# projectElectro.net
KiCad netlist of a schematic drawn in EAGLE
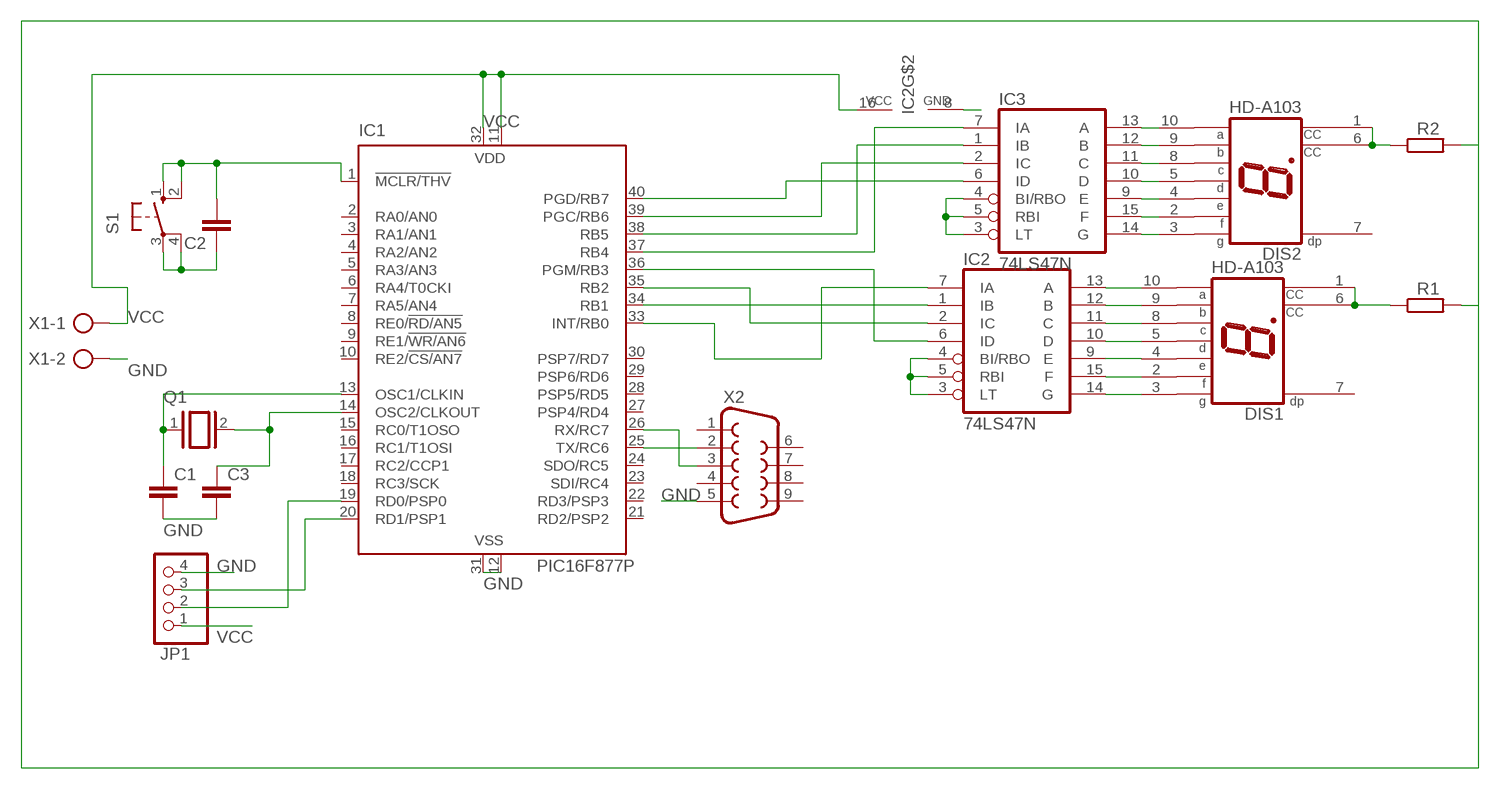
[diagram p0: schematic, sheet 1]

(export (version "E")
  (design (tool "Eeschema 10.0.6"))
  (components
    (comp (ref "C1")
      (value "C-EU025-025X050")
      (footprint "eagle-import:C025-025X050")
      (libsource (lib "eagle-import") (part "C-EU025-025X050"))
    )
    (comp (ref "C2")
      (value "C-EU025-025X050")
      (footprint "eagle-import:C025-025X050")
      (libsource (lib "eagle-import") (part "C-EU025-025X050"))
    )
    (comp (ref "C3")
      (value "C-EU025-025X050")
      (footprint "eagle-import:C025-025X050")
      (libsource (lib "eagle-import") (part "C-EU025-025X050"))
    )
    (comp (ref "DIS1")
      (value "HD-A103")
      (footprint "eagle-import:HDSP-A")
      (libsource (lib "eagle-import") (part "HD-A103"))
    )
    (comp (ref "DIS2")
      (value "HD-A103")
      (footprint "eagle-import:HDSP-A")
      (libsource (lib "eagle-import") (part "HD-A103"))
    )
    (comp (ref "IC1")
      (value "PIC16F877P")
      (footprint "eagle-import:DIL40")
      (fields (field (name "MF") "MICROCHIP") (field (name "MPN") "PIC16F877-04/P"))
      (libsource (lib "eagle-import") (part "PIC16F87P7"))
    )
    (comp (ref "IC2")
      (value "74LS47N")
      (footprint "eagle-import:DIL16")
      (libsource (lib "eagle-import") (part "7447NLS"))
    )
    (comp (ref "IC3")
      (value "74LS47N")
      (footprint "eagle-import:DIL16")
      (libsource (lib "eagle-import") (part "7447NLS"))
    )
    (comp (ref "JP1")
      (value "PINHD-1X4")
      (footprint "eagle-import:1X04")
      (libsource (lib "eagle-import") (part "PINHD-1X4"))
    )
    (comp (ref "Q1")
      (value "XTAL/S")
      (footprint "eagle-import:QS")
      (libsource (lib "eagle-import") (part "XTAL/S"))
    )
    (comp (ref "R1")
      (value "R-EU_0207/10")
      (footprint "eagle-import:0207_10")
      (libsource (lib "eagle-import") (part "R-EU_0207/10"))
    )
    (comp (ref "R2")
      (value "R-EU_0207/10")
      (footprint "eagle-import:0207_10")
      (libsource (lib "eagle-import") (part "R-EU_0207/10"))
    )
    (comp (ref "S1")
      (value "10-XX")
      (footprint "eagle-import:B3F-10XX")
      (fields (field (name "MPN") "B3F-1000"))
      (libsource (lib "eagle-import") (part "10-XX"))
    )
    (comp (ref "X1")
      (value "AK300/2")
      (footprint "eagle-import:AK300_2")
      (libsource (lib "eagle-import") (part "AK300/2"))
    )
    (comp (ref "X2")
      (value "F09H")
      (footprint "eagle-import:F09H")
      (libsource (lib "eagle-import") (part "F09H"))
    )
  )
  (nets
    (net (code "1") (name "/GND") (class "Default")
      (node (ref "C1") (pin "2") (pinfunction "2_2") (pintype "passive"))
      (node (ref "C3") (pin "2") (pinfunction "2_2") (pintype "passive"))
      (node (ref "IC1") (pin "12") (pinfunction "VSS_12") (pintype "power_in"))
      (node (ref "IC1") (pin "31") (pinfunction "VSS_31") (pintype "power_in"))
      (node (ref "JP1") (pin "4") (pinfunction "4_4") (pintype "passive"))
      (node (ref "X1") (pin "2") (pinfunction "KL_2") (pintype "passive"))
      (node (ref "X2") (pin "5") (pinfunction "5_5") (pintype "passive"))
    )
    (net (code "2") (name "/VCC") (class "Default")
      (node (ref "IC1") (pin "11") (pinfunction "VDD_11") (pintype "power_in"))
      (node (ref "IC1") (pin "32") (pinfunction "VDD_32") (pintype "power_in"))
      (node (ref "IC2") (pin "16") (pinfunction "VCC_16") (pintype "power_in"))
      (node (ref "JP1") (pin "1") (pinfunction "1_1") (pintype "passive"))
      (node (ref "X1") (pin "1") (pinfunction "KL_1") (pintype "passive"))
    )
    (net (code "3") (name "Net-(DIS1-A)") (class "Default")
      (node (ref "DIS1") (pin "10") (pinfunction "A_10") (pintype "passive"))
      (node (ref "IC2") (pin "13") (pinfunction "A_13") (pintype "output"))
    )
    (net (code "4") (name "Net-(DIS1-B)") (class "Default")
      (node (ref "DIS1") (pin "9") (pinfunction "B_9") (pintype "passive"))
      (node (ref "IC2") (pin "12") (pinfunction "B_12") (pintype "output"))
    )
    (net (code "5") (name "Net-(DIS1-C)") (class "Default")
      (node (ref "DIS1") (pin "8") (pinfunction "C_8") (pintype "passive"))
      (node (ref "IC2") (pin "11") (pinfunction "C_11") (pintype "output"))
    )
    (net (code "6") (name "Net-(DIS1-CC-Pad1)") (class "Default")
      (node (ref "DIS1") (pin "1") (pinfunction "CC_1") (pintype "passive"))
      (node (ref "DIS1") (pin "6") (pinfunction "CC_6") (pintype "passive"))
      (node (ref "R1") (pin "1") (pinfunction "1_1") (pintype "passive"))
    )
    (net (code "7") (name "Net-(DIS1-D)") (class "Default")
      (node (ref "DIS1") (pin "5") (pinfunction "D_5") (pintype "passive"))
      (node (ref "IC2") (pin "10") (pinfunction "D_10") (pintype "output"))
    )
    (net (code "8") (name "Net-(DIS1-E)") (class "Default")
      (node (ref "DIS1") (pin "4") (pinfunction "E_4") (pintype "passive"))
      (node (ref "IC2") (pin "9") (pinfunction "E_9") (pintype "output"))
    )
    (net (code "9") (name "Net-(DIS1-F)") (class "Default")
      (node (ref "DIS1") (pin "2") (pinfunction "F_2") (pintype "passive"))
      (node (ref "IC2") (pin "15") (pinfunction "F_15") (pintype "output"))
    )
    (net (code "10") (name "Net-(DIS1-G)") (class "Default")
      (node (ref "DIS1") (pin "3") (pinfunction "G_3") (pintype "passive"))
      (node (ref "IC2") (pin "14") (pinfunction "G_14") (pintype "output"))
    )
    (net (code "11") (name "Net-(DIS2-A)") (class "Default")
      (node (ref "DIS2") (pin "10") (pinfunction "A_10") (pintype "passive"))
      (node (ref "IC3") (pin "13") (pinfunction "A_13") (pintype "output"))
    )
    (net (code "12") (name "Net-(DIS2-B)") (class "Default")
      (node (ref "DIS2") (pin "9") (pinfunction "B_9") (pintype "passive"))
      (node (ref "IC3") (pin "12") (pinfunction "B_12") (pintype "output"))
    )
    (net (code "13") (name "Net-(DIS2-C)") (class "Default")
      (node (ref "DIS2") (pin "8") (pinfunction "C_8") (pintype "passive"))
      (node (ref "IC3") (pin "11") (pinfunction "C_11") (pintype "output"))
    )
    (net (code "14") (name "Net-(DIS2-CC-Pad1)") (class "Default")
      (node (ref "DIS2") (pin "1") (pinfunction "CC_1") (pintype "passive"))
      (node (ref "DIS2") (pin "6") (pinfunction "CC_6") (pintype "passive"))
      (node (ref "R2") (pin "1") (pinfunction "1_1") (pintype "passive"))
    )
    (net (code "15") (name "Net-(DIS2-D)") (class "Default")
      (node (ref "DIS2") (pin "5") (pinfunction "D_5") (pintype "passive"))
      (node (ref "IC3") (pin "10") (pinfunction "D_10") (pintype "output"))
    )
    (net (code "16") (name "Net-(DIS2-E)") (class "Default")
      (node (ref "DIS2") (pin "4") (pinfunction "E_4") (pintype "passive"))
      (node (ref "IC3") (pin "9") (pinfunction "E_9") (pintype "output"))
    )
    (net (code "17") (name "Net-(DIS2-F)") (class "Default")
      (node (ref "DIS2") (pin "2") (pinfunction "F_2") (pintype "passive"))
      (node (ref "IC3") (pin "15") (pinfunction "F_15") (pintype "output"))
    )
    (net (code "18") (name "Net-(DIS2-G)") (class "Default")
      (node (ref "DIS2") (pin "3") (pinfunction "G_3") (pintype "passive"))
      (node (ref "IC3") (pin "14") (pinfunction "G_14") (pintype "output"))
    )
    (net (code "19") (name "Net-(IC1-INT{slash}RB0)") (class "Default")
      (node (ref "IC1") (pin "33") (pinfunction "INT/RB0_33") (pintype "bidirectional"))
      (node (ref "IC2") (pin "7") (pinfunction "IA_7") (pintype "input"))
    )
    (net (code "20") (name "Net-(IC1-OSC1{slash}CLKIN)") (class "Default")
      (node (ref "C1") (pin "1") (pinfunction "1_1") (pintype "passive"))
      (node (ref "IC1") (pin "13") (pinfunction "OSC1/CLKIN_13") (pintype "input"))
      (node (ref "Q1") (pin "1") (pinfunction "1_1") (pintype "passive"))
    )
    (net (code "21") (name "Net-(IC1-OSC2{slash}CLKOUT)") (class "Default")
      (node (ref "C3") (pin "1") (pinfunction "1_1") (pintype "passive"))
      (node (ref "IC1") (pin "14") (pinfunction "OSC2/CLKOUT_14") (pintype "output"))
      (node (ref "Q1") (pin "2") (pinfunction "2_2") (pintype "passive"))
    )
    (net (code "22") (name "Net-(IC1-PGC{slash}RB6)") (class "Default")
      (node (ref "IC1") (pin "39") (pinfunction "PGC/RB6_39") (pintype "bidirectional"))
      (node (ref "IC3") (pin "2") (pinfunction "IC_2") (pintype "input"))
    )
    (net (code "23") (name "Net-(IC1-PGD{slash}RB7)") (class "Default")
      (node (ref "IC1") (pin "40") (pinfunction "PGD/RB7_40") (pintype "bidirectional"))
      (node (ref "IC3") (pin "6") (pinfunction "ID_6") (pintype "input"))
    )
    (net (code "24") (name "Net-(IC1-PGM{slash}RB3)") (class "Default")
      (node (ref "IC1") (pin "36") (pinfunction "PGM/RB3_36") (pintype "bidirectional"))
      (node (ref "IC2") (pin "6") (pinfunction "ID_6") (pintype "input"))
    )
    (net (code "25") (name "Net-(IC1-RB1)") (class "Default")
      (node (ref "IC1") (pin "34") (pinfunction "RB1_34") (pintype "bidirectional"))
      (node (ref "IC2") (pin "1") (pinfunction "IB_1") (pintype "input"))
    )
    (net (code "26") (name "Net-(IC1-RB2)") (class "Default")
      (node (ref "IC1") (pin "35") (pinfunction "RB2_35") (pintype "bidirectional"))
      (node (ref "IC2") (pin "2") (pinfunction "IC_2") (pintype "input"))
    )
    (net (code "27") (name "Net-(IC1-RB4)") (class "Default")
      (node (ref "IC1") (pin "37") (pinfunction "RB4_37") (pintype "bidirectional"))
      (node (ref "IC3") (pin "7") (pinfunction "IA_7") (pintype "input"))
    )
    (net (code "28") (name "Net-(IC1-RB5)") (class "Default")
      (node (ref "IC1") (pin "38") (pinfunction "RB5_38") (pintype "bidirectional"))
      (node (ref "IC3") (pin "1") (pinfunction "IB_1") (pintype "input"))
    )
    (net (code "29") (name "Net-(IC1-RD0{slash}PSP0)") (class "Default")
      (node (ref "IC1") (pin "19") (pinfunction "RD0/PSP0_19") (pintype "bidirectional"))
      (node (ref "JP1") (pin "2") (pinfunction "2_2") (pintype "passive"))
    )
    (net (code "30") (name "Net-(IC1-RD1{slash}PSP1)") (class "Default")
      (node (ref "IC1") (pin "20") (pinfunction "RD1/PSP1_20") (pintype "bidirectional"))
      (node (ref "JP1") (pin "3") (pinfunction "3_3") (pintype "passive"))
    )
    (net (code "31") (name "Net-(IC1-RX{slash}RC7)") (class "Default")
      (node (ref "IC1") (pin "26") (pinfunction "RX/RC7_26") (pintype "bidirectional"))
      (node (ref "X2") (pin "3") (pinfunction "3_3") (pintype "passive"))
    )
    (net (code "32") (name "Net-(IC1-TX{slash}RC6)") (class "Default")
      (node (ref "IC1") (pin "25") (pinfunction "TX/RC6_25") (pintype "bidirectional"))
      (node (ref "X2") (pin "2") (pinfunction "2_2") (pintype "passive"))
    )
    (net (code "33") (name "Net-(IC1-~{MCLR{slash}THV})") (class "Default")
      (node (ref "C2") (pin "2") (pinfunction "2_2") (pintype "passive"))
      (node (ref "IC1") (pin "1") (pinfunction "~{MCLR/THV}_1") (pintype "input"))
      (node (ref "S1") (pin "1") (pinfunction "S_1") (pintype "passive"))
      (node (ref "S1") (pin "2") (pinfunction "S1_2") (pintype "passive"))
    )
    (net (code "34") (name "Net-(IC2A-BI{slash}RBO)") (class "Default")
      (node (ref "IC2") (pin "3") (pinfunction "LT_3") (pintype "input"))
      (node (ref "IC2") (pin "4") (pinfunction "BI/RBO_4") (pintype "input"))
      (node (ref "IC2") (pin "5") (pinfunction "RBI_5") (pintype "input"))
    )
    (net (code "35") (name "Net-(IC3A-BI{slash}RBO)") (class "Default")
      (node (ref "IC3") (pin "3") (pinfunction "LT_3") (pintype "input"))
      (node (ref "IC3") (pin "4") (pinfunction "BI/RBO_4") (pintype "input"))
      (node (ref "IC3") (pin "5") (pinfunction "RBI_5") (pintype "input"))
    )
    (net (code "36") (name "Net-(S1-P)") (class "Default")
      (node (ref "C2") (pin "1") (pinfunction "1_1") (pintype "passive"))
      (node (ref "S1") (pin "3") (pinfunction "P_3") (pintype "passive"))
      (node (ref "S1") (pin "4") (pinfunction "P1_4") (pintype "passive"))
    )
    (net (code "37") (name "unconnected-(DIS1-DP-Pad7)") (class "Default")
      (node (ref "DIS1") (pin "7") (pinfunction "DP_7") (pintype "passive"))
    )
    (net (code "38") (name "unconnected-(DIS2-DP-Pad7)") (class "Default")
      (node (ref "DIS2") (pin "7") (pinfunction "DP_7") (pintype "passive"))
    )
    (net (code "39") (name "unconnected-(IC1-PSP4{slash}RD4-Pad27)") (class "Default")
      (node (ref "IC1") (pin "27") (pinfunction "PSP4/RD4_27") (pintype "bidirectional"))
    )
    (net (code "40") (name "unconnected-(IC1-PSP5{slash}RD5-Pad28)") (class "Default")
      (node (ref "IC1") (pin "28") (pinfunction "PSP5/RD5_28") (pintype "bidirectional"))
    )
    (net (code "41") (name "unconnected-(IC1-PSP6{slash}RD6-Pad29)") (class "Default")
      (node (ref "IC1") (pin "29") (pinfunction "PSP6/RD6_29") (pintype "bidirectional"))
    )
    (net (code "42") (name "unconnected-(IC1-PSP7{slash}RD7-Pad30)") (class "Default")
      (node (ref "IC1") (pin "30") (pinfunction "PSP7/RD7_30") (pintype "bidirectional"))
    )
    (net (code "43") (name "unconnected-(IC1-RA0{slash}AN0-Pad2)") (class "Default")
      (node (ref "IC1") (pin "2") (pinfunction "RA0/AN0_2") (pintype "bidirectional"))
    )
    (net (code "44") (name "unconnected-(IC1-RA1{slash}AN1-Pad3)") (class "Default")
      (node (ref "IC1") (pin "3") (pinfunction "RA1/AN1_3") (pintype "bidirectional"))
    )
    (net (code "45") (name "unconnected-(IC1-RA2{slash}AN2-Pad4)") (class "Default")
      (node (ref "IC1") (pin "4") (pinfunction "RA2/AN2_4") (pintype "bidirectional"))
    )
    (net (code "46") (name "unconnected-(IC1-RA3{slash}AN3-Pad5)") (class "Default")
      (node (ref "IC1") (pin "5") (pinfunction "RA3/AN3_5") (pintype "bidirectional"))
    )
    (net (code "47") (name "unconnected-(IC1-RA4{slash}T0CKI-Pad6)") (class "Default")
      (node (ref "IC1") (pin "6") (pinfunction "RA4/T0CKI_6") (pintype "bidirectional"))
    )
    (net (code "48") (name "unconnected-(IC1-RA5{slash}AN4-Pad7)") (class "Default")
      (node (ref "IC1") (pin "7") (pinfunction "RA5/AN4_7") (pintype "bidirectional"))
    )
    (net (code "49") (name "unconnected-(IC1-RC0{slash}T1OSO-Pad15)") (class "Default")
      (node (ref "IC1") (pin "15") (pinfunction "RC0/T1OSO_15") (pintype "bidirectional"))
    )
    (net (code "50") (name "unconnected-(IC1-RC1{slash}T1OSI-Pad16)") (class "Default")
      (node (ref "IC1") (pin "16") (pinfunction "RC1/T1OSI_16") (pintype "bidirectional"))
    )
    (net (code "51") (name "unconnected-(IC1-RC2{slash}CCP1-Pad17)") (class "Default")
      (node (ref "IC1") (pin "17") (pinfunction "RC2/CCP1_17") (pintype "bidirectional"))
    )
    (net (code "52") (name "unconnected-(IC1-RC3{slash}SCK-Pad18)") (class "Default")
      (node (ref "IC1") (pin "18") (pinfunction "RC3/SCK_18") (pintype "bidirectional"))
    )
    (net (code "53") (name "unconnected-(IC1-RD2{slash}PSP2-Pad21)") (class "Default")
      (node (ref "IC1") (pin "21") (pinfunction "RD2/PSP2_21") (pintype "bidirectional"))
    )
    (net (code "54") (name "unconnected-(IC1-RD3{slash}PSP3-Pad22)") (class "Default")
      (node (ref "IC1") (pin "22") (pinfunction "RD3/PSP3_22") (pintype "bidirectional"))
    )
    (net (code "55") (name "unconnected-(IC1-RE0{slash}~{RD{slash}AN5}-Pad8)") (class "Default")
      (node (ref "IC1") (pin "8") (pinfunction "RE0/~{RD/AN5}_8") (pintype "bidirectional"))
    )
    (net (code "56") (name "unconnected-(IC1-RE1{slash}~{WR{slash}AN6}-Pad9)") (class "Default")
      (node (ref "IC1") (pin "9") (pinfunction "RE1/~{WR/AN6}_9") (pintype "bidirectional"))
    )
    (net (code "57") (name "unconnected-(IC1-RE2{slash}~{CS{slash}AN7}-Pad10)") (class "Default")
      (node (ref "IC1") (pin "10") (pinfunction "RE2/~{CS/AN7}_10") (pintype "bidirectional"))
    )
    (net (code "58") (name "unconnected-(IC1-SDI{slash}RC4-Pad23)") (class "Default")
      (node (ref "IC1") (pin "23") (pinfunction "SDI/RC4_23") (pintype "bidirectional"))
    )
    (net (code "59") (name "unconnected-(IC1-SDO{slash}RC5-Pad24)") (class "Default")
      (node (ref "IC1") (pin "24") (pinfunction "SDO/RC5_24") (pintype "bidirectional"))
    )
    (net (code "60") (name "unconnected-(IC2B-GND-Pad8)") (class "Default")
      (node (ref "IC2") (pin "8") (pinfunction "GND_8") (pintype "power_in"))
    )
    (net (code "61") (name "unconnected-(R1-Pad2)") (class "Default")
      (node (ref "R1") (pin "2") (pinfunction "2_2") (pintype "passive"))
    )
    (net (code "62") (name "unconnected-(R2-Pad2)") (class "Default")
      (node (ref "R2") (pin "2") (pinfunction "2_2") (pintype "passive"))
    )
    (net (code "63") (name "unconnected-(X2-Pad1)") (class "Default")
      (node (ref "X2") (pin "1") (pinfunction "1_1") (pintype "passive"))
    )
    (net (code "64") (name "unconnected-(X2-Pad4)") (class "Default")
      (node (ref "X2") (pin "4") (pinfunction "4_4") (pintype "passive"))
    )
    (net (code "65") (name "unconnected-(X2-Pad6)") (class "Default")
      (node (ref "X2") (pin "6") (pinfunction "6_6") (pintype "passive"))
    )
    (net (code "66") (name "unconnected-(X2-Pad7)") (class "Default")
      (node (ref "X2") (pin "7") (pinfunction "7_7") (pintype "passive"))
    )
    (net (code "67") (name "unconnected-(X2-Pad8)") (class "Default")
      (node (ref "X2") (pin "8") (pinfunction "8_8") (pintype "passive"))
    )
    (net (code "68") (name "unconnected-(X2-Pad9)") (class "Default")
      (node (ref "X2") (pin "9") (pinfunction "9_9") (pintype "passive"))
    )
  )
)
